# HyperLight_S_rev1_0.net
KiCad netlist of a schematic drawn in EAGLE
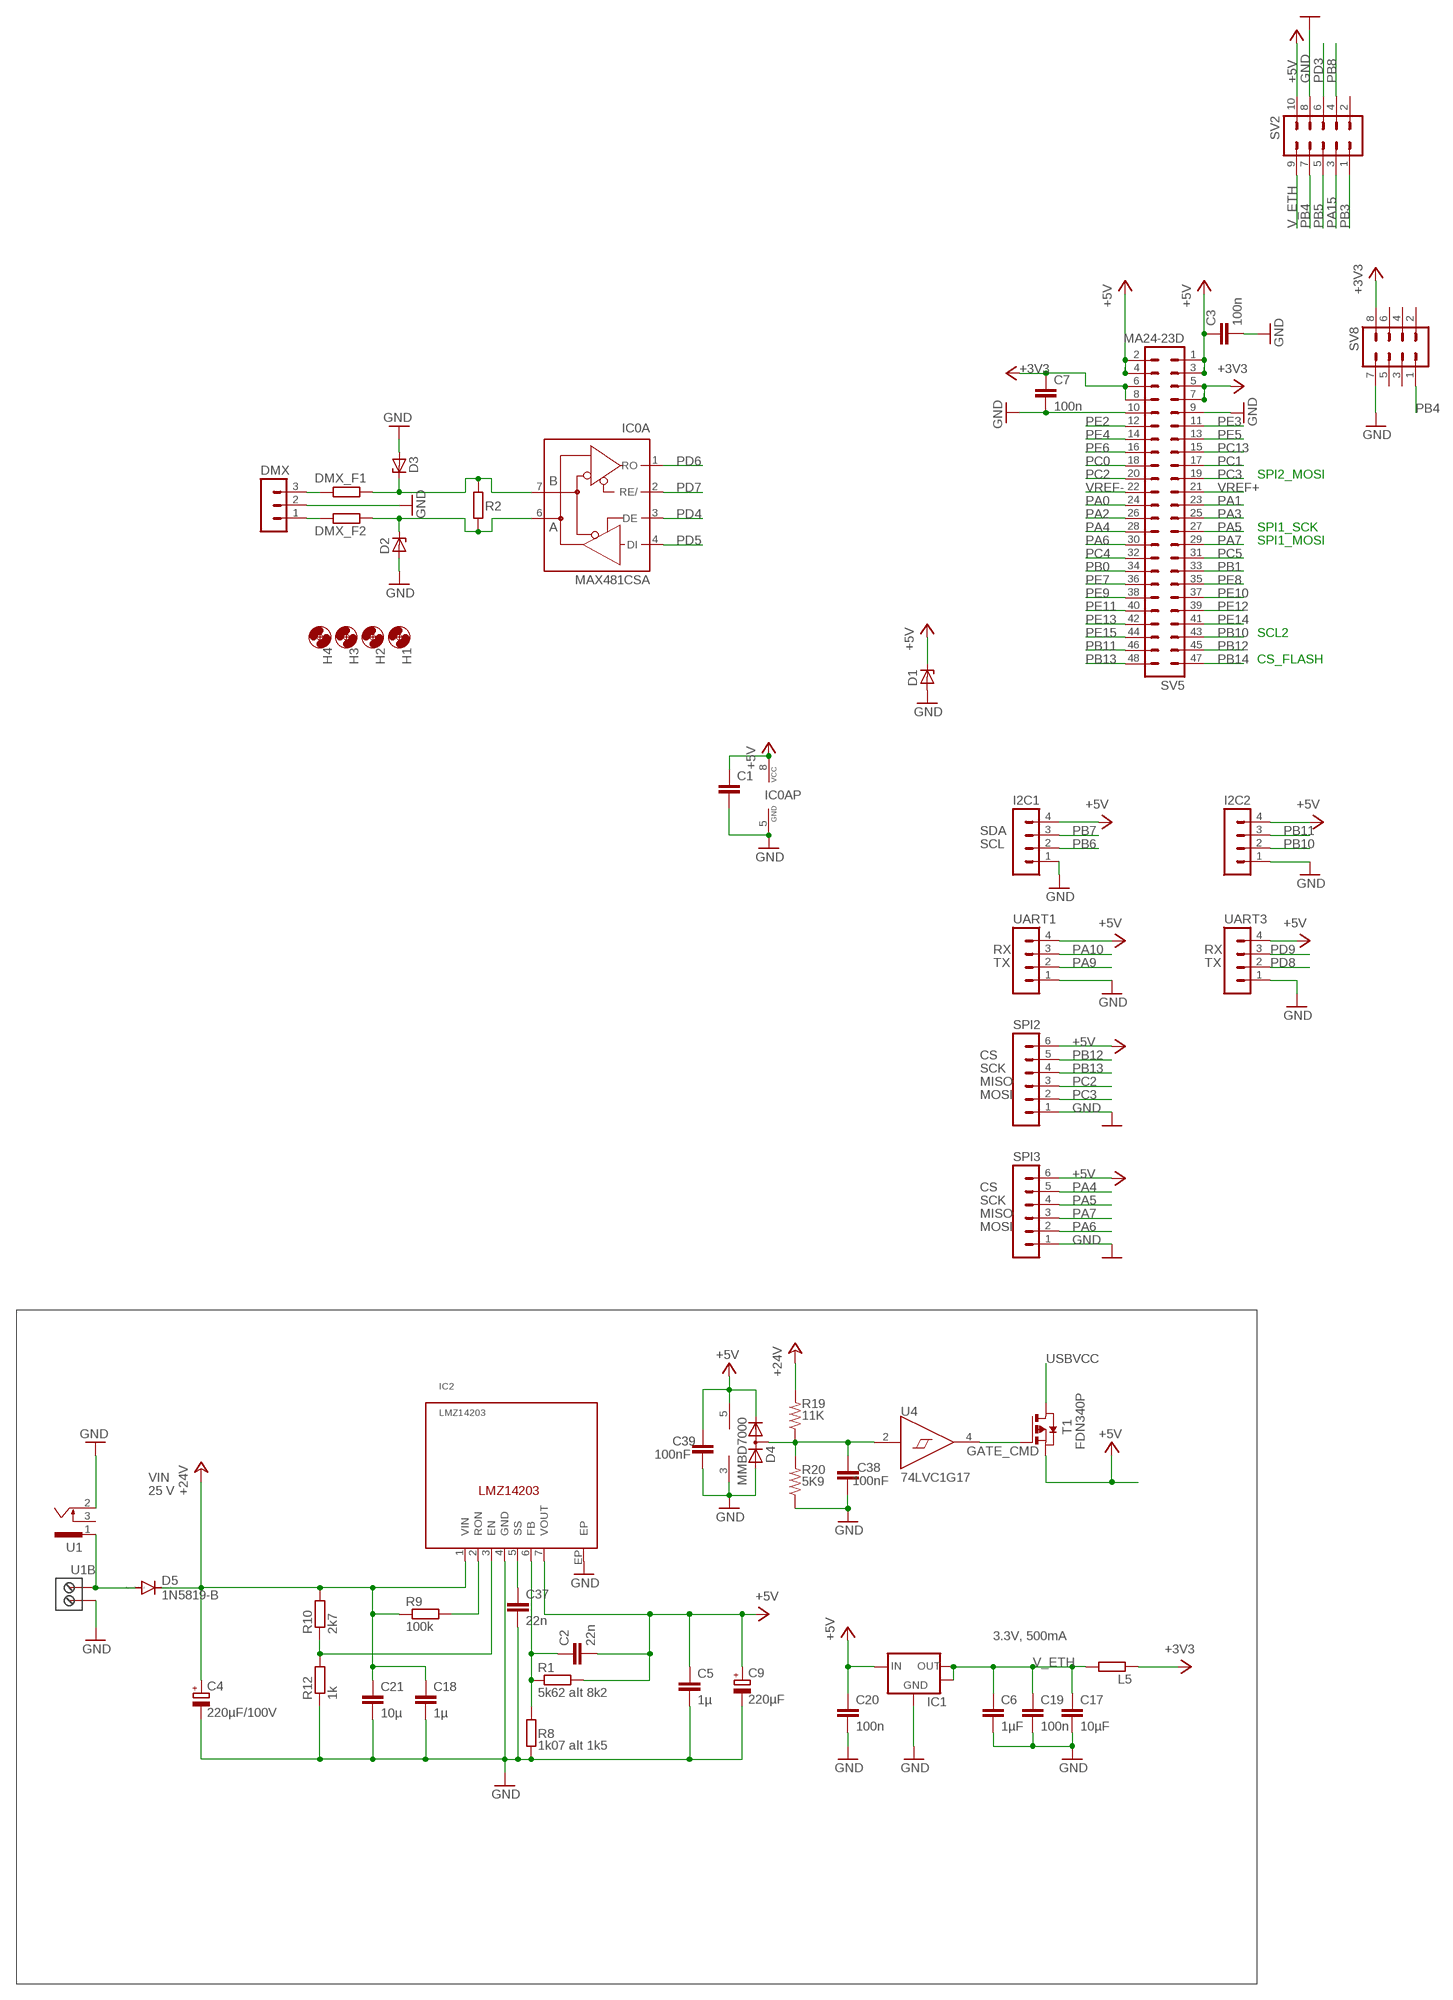
[diagram p0: schematic, sheet 1, part 1 of 2]
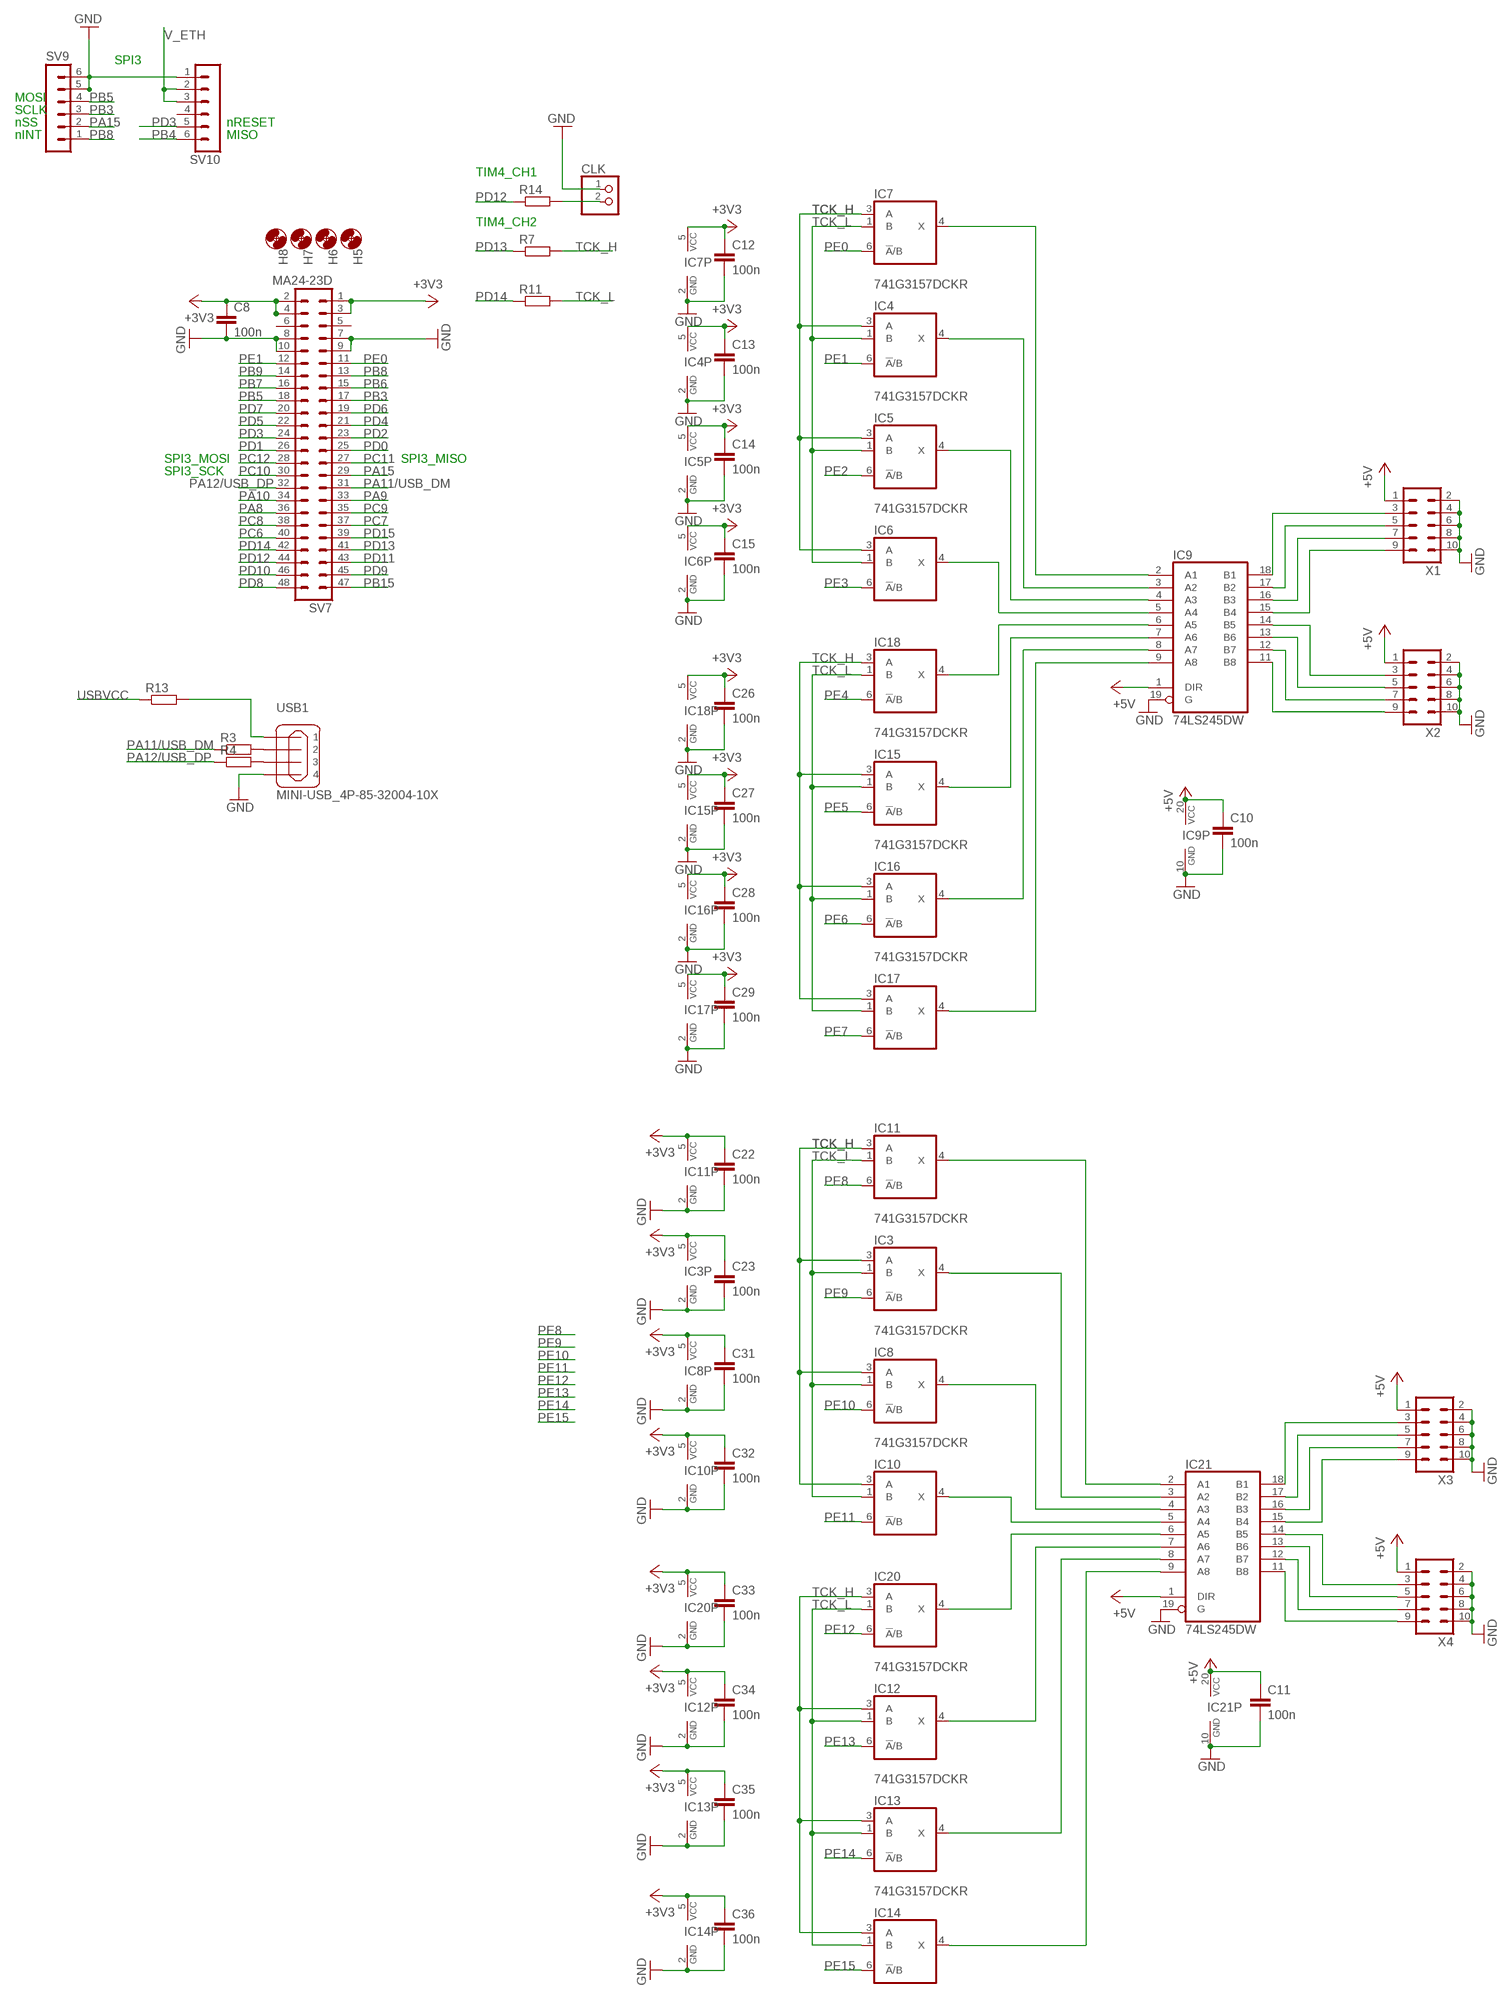
[diagram p1: schematic, sheet 1, part 2 of 2]

(export (version "E")
  (design (tool "Eeschema 10.0.6"))
  (components
    (comp (ref "C1")
      (value "C-EUC0805")
      (footprint "eagle-import:C0805")
      (libsource (lib "eagle-import") (part "rcl_C-EUC0805"))
    )
    (comp (ref "C2")
      (value "22n")
      (footprint "eagle-import:C0805")
      (libsource (lib "eagle-import") (part "rcl_334_C-EUC0805"))
    )
    (comp (ref "C3")
      (value "100n")
      (footprint "eagle-import:C0805")
      (libsource (lib "eagle-import") (part "rcl_334_C-EUC0805"))
    )
    (comp (ref "C4")
      (value "220µF/100V")
      (footprint "eagle-import:153CLV-0810")
      (libsource (lib "eagle-import") (part "CPOL-EU153CLV-0810"))
    )
    (comp (ref "C5")
      (value "1µ")
      (footprint "eagle-import:C0805")
      (libsource (lib "eagle-import") (part "rcl_334_C-EUC0805"))
    )
    (comp (ref "C6")
      (value "1µF")
      (footprint "eagle-import:C0805")
      (fields (field (name "SPICEPREFIX") "C"))
      (libsource (lib "eagle-import") (part "rcl_334_C-EUC0805"))
    )
    (comp (ref "C7")
      (value "100n")
      (footprint "eagle-import:C0805")
      (libsource (lib "eagle-import") (part "rcl_334_C-EUC0805"))
    )
    (comp (ref "C8")
      (value "100n")
      (footprint "eagle-import:C0805")
      (libsource (lib "eagle-import") (part "rcl_334_C-EUC0805"))
    )
    (comp (ref "C9")
      (value "220µF")
      (footprint "eagle-import:153CLV-0810")
      (libsource (lib "eagle-import") (part "CPOL-EU153CLV-0810"))
    )
    (comp (ref "C10")
      (value "100n")
      (footprint "eagle-import:C0603")
      (libsource (lib "eagle-import") (part "rcl_C-EUC0603"))
    )
    (comp (ref "C11")
      (value "100n")
      (footprint "eagle-import:C0603")
      (libsource (lib "eagle-import") (part "rcl_C-EUC0603"))
    )
    (comp (ref "C12")
      (value "100n")
      (footprint "eagle-import:C0603")
      (libsource (lib "eagle-import") (part "rcl_C-EUC0603"))
    )
    (comp (ref "C13")
      (value "100n")
      (footprint "eagle-import:C0603")
      (libsource (lib "eagle-import") (part "rcl_C-EUC0603"))
    )
    (comp (ref "C14")
      (value "100n")
      (footprint "eagle-import:C0603")
      (libsource (lib "eagle-import") (part "rcl_C-EUC0603"))
    )
    (comp (ref "C15")
      (value "100n")
      (footprint "eagle-import:C0603")
      (libsource (lib "eagle-import") (part "rcl_C-EUC0603"))
    )
    (comp (ref "C17")
      (value "10µF")
      (footprint "eagle-import:C0805")
      (fields (field (name "SPICEPREFIX") "C"))
      (libsource (lib "eagle-import") (part "rcl_334_C-EUC0805"))
    )
    (comp (ref "C18")
      (value "1µ")
      (footprint "eagle-import:C0805")
      (libsource (lib "eagle-import") (part "rcl_334_C-EUC0805"))
    )
    (comp (ref "C19")
      (value "100n")
      (footprint "eagle-import:C0805")
      (fields (field (name "SPICEPREFIX") "C"))
      (libsource (lib "eagle-import") (part "rcl_334_C-EUC0805"))
    )
    (comp (ref "C20")
      (value "100n")
      (footprint "eagle-import:C0805")
      (libsource (lib "eagle-import") (part "rcl_334_C-EUC0805"))
    )
    (comp (ref "C21")
      (value "10µ")
      (footprint "eagle-import:C0805")
      (libsource (lib "eagle-import") (part "rcl_334_C-EUC0805"))
    )
    (comp (ref "C22")
      (value "100n")
      (footprint "eagle-import:C0603")
      (libsource (lib "eagle-import") (part "rcl_C-EUC0603"))
    )
    (comp (ref "C23")
      (value "100n")
      (footprint "eagle-import:C0603")
      (libsource (lib "eagle-import") (part "rcl_C-EUC0603"))
    )
    (comp (ref "C26")
      (value "100n")
      (footprint "eagle-import:C0603")
      (libsource (lib "eagle-import") (part "rcl_C-EUC0603"))
    )
    (comp (ref "C27")
      (value "100n")
      (footprint "eagle-import:C0603")
      (libsource (lib "eagle-import") (part "rcl_C-EUC0603"))
    )
    (comp (ref "C28")
      (value "100n")
      (footprint "eagle-import:C0603")
      (libsource (lib "eagle-import") (part "rcl_C-EUC0603"))
    )
    (comp (ref "C29")
      (value "100n")
      (footprint "eagle-import:C0603")
      (libsource (lib "eagle-import") (part "rcl_C-EUC0603"))
    )
    (comp (ref "C31")
      (value "100n")
      (footprint "eagle-import:C0603")
      (libsource (lib "eagle-import") (part "rcl_C-EUC0603"))
    )
    (comp (ref "C32")
      (value "100n")
      (footprint "eagle-import:C0603")
      (libsource (lib "eagle-import") (part "rcl_C-EUC0603"))
    )
    (comp (ref "C33")
      (value "100n")
      (footprint "eagle-import:C0603")
      (libsource (lib "eagle-import") (part "rcl_C-EUC0603"))
    )
    (comp (ref "C34")
      (value "100n")
      (footprint "eagle-import:C0603")
      (libsource (lib "eagle-import") (part "rcl_C-EUC0603"))
    )
    (comp (ref "C35")
      (value "100n")
      (footprint "eagle-import:C0603")
      (libsource (lib "eagle-import") (part "rcl_C-EUC0603"))
    )
    (comp (ref "C36")
      (value "100n")
      (footprint "eagle-import:C0603")
      (libsource (lib "eagle-import") (part "rcl_C-EUC0603"))
    )
    (comp (ref "C37")
      (value "22n")
      (footprint "eagle-import:C0805")
      (libsource (lib "eagle-import") (part "rcl_334_C-EUC0805"))
    )
    (comp (ref "C38")
      (value "100nF")
      (footprint "eagle-import:C0402")
      (libsource (lib "eagle-import") (part "C-EUC0402"))
    )
    (comp (ref "C39")
      (value "100nF")
      (footprint "eagle-import:C0402")
      (libsource (lib "eagle-import") (part "rcl_C-EUC0402"))
    )
    (comp (ref "CLK")
      (value "PINHD-1X2")
      (footprint "eagle-import:1X02")
      (libsource (lib "eagle-import") (part "PINHD-1X2"))
    )
    (comp (ref "D1")
      (value "ZENER-DIODESMB")
      (footprint "eagle-import:SMB")
      (libsource (lib "eagle-import") (part "ZENER-DIODESMB"))
    )
    (comp (ref "D2")
      (value "ZENER-DIODESMB")
      (footprint "eagle-import:SMB")
      (libsource (lib "eagle-import") (part "ZENER-DIODESMB"))
    )
    (comp (ref "D3")
      (value "ZENER-DIODESMB")
      (footprint "eagle-import:SMB")
      (libsource (lib "eagle-import") (part "ZENER-DIODESMB"))
    )
    (comp (ref "D4")
      (value "MMBD7000")
      (footprint "eagle-import:SC70-3-R")
      (libsource (lib "eagle-import") (part "BAV199W"))
    )
    (comp (ref "D5")
      (value "1N5819-B")
      (footprint "eagle-import:SMB")
      (libsource (lib "eagle-import") (part "ES2D"))
    )
    (comp (ref "DMX")
      (value "MA03-1")
      (footprint "eagle-import:MA03-1")
      (libsource (lib "eagle-import") (part "MA03-1"))
    )
    (comp (ref "DMX_F1")
      (value "R-EU_R0805")
      (footprint "eagle-import:R0805@1")
      (libsource (lib "eagle-import") (part "R-EU_R0805"))
    )
    (comp (ref "DMX_F2")
      (value "R-EU_R0805")
      (footprint "eagle-import:R0805@1")
      (libsource (lib "eagle-import") (part "R-EU_R0805"))
    )
    (comp (ref "H1")
      (value "MOUNT-HOLE3.2")
      (footprint "eagle-import:3,2")
      (libsource (lib "eagle-import") (part "MOUNT-HOLE3.2"))
    )
    (comp (ref "H2")
      (value "MOUNT-HOLE3.2")
      (footprint "eagle-import:3,2")
      (libsource (lib "eagle-import") (part "MOUNT-HOLE3.2"))
    )
    (comp (ref "H3")
      (value "MOUNT-HOLE3.2")
      (footprint "eagle-import:3,2")
      (libsource (lib "eagle-import") (part "MOUNT-HOLE3.2"))
    )
    (comp (ref "H4")
      (value "MOUNT-HOLE3.2")
      (footprint "eagle-import:3,2")
      (libsource (lib "eagle-import") (part "MOUNT-HOLE3.2"))
    )
    (comp (ref "H5")
      (value "MOUNT-HOLE3.2")
      (footprint "eagle-import:3,2")
      (libsource (lib "eagle-import") (part "MOUNT-HOLE3.2"))
    )
    (comp (ref "H6")
      (value "MOUNT-HOLE3.2")
      (footprint "eagle-import:3,2")
      (libsource (lib "eagle-import") (part "MOUNT-HOLE3.2"))
    )
    (comp (ref "H7")
      (value "MOUNT-HOLE3.2")
      (footprint "eagle-import:3,2")
      (libsource (lib "eagle-import") (part "MOUNT-HOLE3.2"))
    )
    (comp (ref "H8")
      (value "MOUNT-HOLE3.2")
      (footprint "eagle-import:3,2")
      (libsource (lib "eagle-import") (part "MOUNT-HOLE3.2"))
    )
    (comp (ref "I2C1")
      (value "MA04-1")
      (footprint "eagle-import:MA04-1")
      (libsource (lib "eagle-import") (part "MA04-1"))
    )
    (comp (ref "I2C2")
      (value "MA04-1")
      (footprint "eagle-import:MA04-1")
      (libsource (lib "eagle-import") (part "MA04-1"))
    )
    (comp (ref "IC0A")
      (value "MAX481CSA")
      (footprint "eagle-import:SO08")
      (fields (field (name "MF") "MAXIM"))
      (libsource (lib "eagle-import") (part "MAX481CSA"))
    )
    (comp (ref "IC1")
      (value "LM1117")
      (footprint "eagle-import:SOT223")
      (libsource (lib "eagle-import") (part "LM1117"))
    )
    (comp (ref "IC2")
      (value "LMZ14203")
      (footprint "eagle-import:TO-PMOD")
      (libsource (lib "eagle-import") (part "LMZ14203"))
    )
    (comp (ref "IC3")
      (value "741G3157DCKR")
      (footprint "eagle-import:DCK_R-PDSO-G6")
      (libsource (lib "eagle-import") (part "741G3157DCKR"))
    )
    (comp (ref "IC4")
      (value "741G3157DCKR")
      (footprint "eagle-import:DCK_R-PDSO-G6")
      (libsource (lib "eagle-import") (part "741G3157DCKR"))
    )
    (comp (ref "IC5")
      (value "741G3157DCKR")
      (footprint "eagle-import:DCK_R-PDSO-G6")
      (libsource (lib "eagle-import") (part "741G3157DCKR"))
    )
    (comp (ref "IC6")
      (value "741G3157DCKR")
      (footprint "eagle-import:DCK_R-PDSO-G6")
      (libsource (lib "eagle-import") (part "741G3157DCKR"))
    )
    (comp (ref "IC7")
      (value "741G3157DCKR")
      (footprint "eagle-import:DCK_R-PDSO-G6")
      (libsource (lib "eagle-import") (part "741G3157DCKR"))
    )
    (comp (ref "IC8")
      (value "741G3157DCKR")
      (footprint "eagle-import:DCK_R-PDSO-G6")
      (libsource (lib "eagle-import") (part "741G3157DCKR"))
    )
    (comp (ref "IC9")
      (value "74LS245DW")
      (footprint "eagle-import:SO20W")
      (libsource (lib "eagle-import") (part "74245DWLS"))
    )
    (comp (ref "IC10")
      (value "741G3157DCKR")
      (footprint "eagle-import:DCK_R-PDSO-G6")
      (libsource (lib "eagle-import") (part "741G3157DCKR"))
    )
    (comp (ref "IC11")
      (value "741G3157DCKR")
      (footprint "eagle-import:DCK_R-PDSO-G6")
      (libsource (lib "eagle-import") (part "741G3157DCKR"))
    )
    (comp (ref "IC12")
      (value "741G3157DCKR")
      (footprint "eagle-import:DCK_R-PDSO-G6")
      (libsource (lib "eagle-import") (part "741G3157DCKR"))
    )
    (comp (ref "IC13")
      (value "741G3157DCKR")
      (footprint "eagle-import:DCK_R-PDSO-G6")
      (libsource (lib "eagle-import") (part "741G3157DCKR"))
    )
    (comp (ref "IC14")
      (value "741G3157DCKR")
      (footprint "eagle-import:DCK_R-PDSO-G6")
      (libsource (lib "eagle-import") (part "741G3157DCKR"))
    )
    (comp (ref "IC15")
      (value "741G3157DCKR")
      (footprint "eagle-import:DCK_R-PDSO-G6")
      (libsource (lib "eagle-import") (part "741G3157DCKR"))
    )
    (comp (ref "IC16")
      (value "741G3157DCKR")
      (footprint "eagle-import:DCK_R-PDSO-G6")
      (libsource (lib "eagle-import") (part "741G3157DCKR"))
    )
    (comp (ref "IC17")
      (value "741G3157DCKR")
      (footprint "eagle-import:DCK_R-PDSO-G6")
      (libsource (lib "eagle-import") (part "741G3157DCKR"))
    )
    (comp (ref "IC18")
      (value "741G3157DCKR")
      (footprint "eagle-import:DCK_R-PDSO-G6")
      (libsource (lib "eagle-import") (part "741G3157DCKR"))
    )
    (comp (ref "IC20")
      (value "741G3157DCKR")
      (footprint "eagle-import:DCK_R-PDSO-G6")
      (libsource (lib "eagle-import") (part "741G3157DCKR"))
    )
    (comp (ref "IC21")
      (value "74LS245DW")
      (footprint "eagle-import:SO20W")
      (libsource (lib "eagle-import") (part "74245DWLS"))
    )
    (comp (ref "L5")
      (value "R-EU_R0603")
      (footprint "eagle-import:R0603")
      (libsource (lib "eagle-import") (part "rcl_334_R-EU_R0603"))
    )
    (comp (ref "R1")
      (value "5k62 alt 8k2")
      (footprint "eagle-import:R0805@1")
      (libsource (lib "eagle-import") (part "R-EU_R0805"))
    )
    (comp (ref "R2")
      (value "R-EU_R0805")
      (footprint "eagle-import:R0805@1")
      (libsource (lib "eagle-import") (part "R-EU_R0805"))
    )
    (comp (ref "R3")
      (value "R-EU_R0805")
      (footprint "eagle-import:R0805@1")
      (libsource (lib "eagle-import") (part "R-EU_R0805"))
    )
    (comp (ref "R4")
      (value "R-EU_R0805")
      (footprint "eagle-import:R0805@1")
      (libsource (lib "eagle-import") (part "R-EU_R0805"))
    )
    (comp (ref "R7")
      (value "R-EU_R0805")
      (footprint "eagle-import:R0805@1")
      (libsource (lib "eagle-import") (part "R-EU_R0805"))
    )
    (comp (ref "R8")
      (value "1k07 alt 1k5")
      (footprint "eagle-import:R0805@1")
      (libsource (lib "eagle-import") (part "R-EU_R0805"))
    )
    (comp (ref "R9")
      (value "100k")
      (footprint "eagle-import:R0805@1")
      (libsource (lib "eagle-import") (part "R-EU_R0805"))
    )
    (comp (ref "R10")
      (value "2k7")
      (footprint "eagle-import:R0805@1")
      (libsource (lib "eagle-import") (part "R-EU_R0805"))
    )
    (comp (ref "R11")
      (value "R-EU_R0805")
      (footprint "eagle-import:R0805@1")
      (libsource (lib "eagle-import") (part "R-EU_R0805"))
    )
    (comp (ref "R12")
      (value "1k")
      (footprint "eagle-import:R0805@1")
      (libsource (lib "eagle-import") (part "R-EU_R0805"))
    )
    (comp (ref "R13")
      (value "R-EU_R1206")
      (footprint "eagle-import:R1206@1")
      (libsource (lib "eagle-import") (part "R-EU_R1206"))
    )
    (comp (ref "R14")
      (value "R-EU_R0805")
      (footprint "eagle-import:R0805@1")
      (libsource (lib "eagle-import") (part "R-EU_R0805"))
    )
    (comp (ref "R19")
      (value "11K")
      (footprint "eagle-import:R0402")
      (libsource (lib "eagle-import") (part "R-US_R0402"))
    )
    (comp (ref "R20")
      (value "5K9")
      (footprint "eagle-import:R0402")
      (libsource (lib "eagle-import") (part "R-US_R0402"))
    )
    (comp (ref "SPI2")
      (value "MA06-1")
      (footprint "eagle-import:MA06-1")
      (libsource (lib "eagle-import") (part "MA06-1"))
    )
    (comp (ref "SPI3")
      (value "MA06-1")
      (footprint "eagle-import:MA06-1")
      (libsource (lib "eagle-import") (part "MA06-1"))
    )
    (comp (ref "SV2")
      (value "MA05-2")
      (footprint "eagle-import:MA05-2")
      (libsource (lib "eagle-import") (part "MA05-2"))
    )
    (comp (ref "SV5")
      (value "MA24-23D")
      (footprint "eagle-import:HDRVR48W64P254_2X24_6096X508X762B")
      (libsource (lib "eagle-import") (part "MA24-23D"))
    )
    (comp (ref "SV7")
      (value "MA24-23D")
      (footprint "eagle-import:HDRVR48W64P254_2X24_6096X508X762B")
      (libsource (lib "eagle-import") (part "MA24-23D"))
    )
    (comp (ref "SV8")
      (value "MA04-2MALE_3D")
      (footprint "eagle-import:HDRV8W64P254_2X4_1016X508X838B")
      (libsource (lib "eagle-import") (part "MA04-2MALE_3D"))
    )
    (comp (ref "SV9")
      (value "MA06-1FEMALE_3D")
      (footprint "eagle-import:HDRVR6W64P254_1X6_1524X254X762B")
      (libsource (lib "eagle-import") (part "MA06-1FEMALE_3D"))
    )
    (comp (ref "SV10")
      (value "MA06-1FEMALE_3D")
      (footprint "eagle-import:HDRVR6W64P254_1X6_1524X254X762B")
      (libsource (lib "eagle-import") (part "MA06-1FEMALE_3D"))
    )
    (comp (ref "T1")
      (value "FDN340P")
      (footprint "eagle-import:SOT-23")
      (libsource (lib "eagle-import") (part "PMOSSOT23"))
    )
    (comp (ref "U1")
      (value "733980-62")
      (footprint "eagle-import:733980-62")
      (libsource (lib "eagle-import") (part "73398?0-62"))
    )
    (comp (ref "U1B")
      (value "RIACON101-02")
      (footprint "eagle-import:RIACON101-02")
      (libsource (lib "eagle-import") (part "RIACON101-02"))
    )
    (comp (ref "U4")
      (value "74LVC1G17")
      (footprint "eagle-import:SOT-553")
      (libsource (lib "eagle-import") (part "74LVC1G17"))
    )
    (comp (ref "UART1")
      (value "MA04-1")
      (footprint "eagle-import:MA04-1")
      (libsource (lib "eagle-import") (part "MA04-1"))
    )
    (comp (ref "UART3")
      (value "MA04-1")
      (footprint "eagle-import:MA04-1")
      (libsource (lib "eagle-import") (part "MA04-1"))
    )
    (comp (ref "USB1")
      (value "MINI-USB_4P-85-32004-10X")
      (footprint "eagle-import:85-32004-10X")
      (libsource (lib "eagle-import") (part "MINI-USB_4P-85-32004-10X"))
    )
    (comp (ref "X1")
      (value "MA05-2MA05-2S")
      (footprint "eagle-import:MA05-2S")
      (libsource (lib "eagle-import") (part "MA05-2MA05-2S"))
    )
    (comp (ref "X2")
      (value "MA05-2MA05-2S")
      (footprint "eagle-import:MA05-2S")
      (libsource (lib "eagle-import") (part "MA05-2MA05-2S"))
    )
    (comp (ref "X3")
      (value "MA05-2MA05-2S")
      (footprint "eagle-import:MA05-2S")
      (libsource (lib "eagle-import") (part "MA05-2MA05-2S"))
    )
    (comp (ref "X4")
      (value "MA05-2MA05-2S")
      (footprint "eagle-import:MA05-2S")
      (libsource (lib "eagle-import") (part "MA05-2MA05-2S"))
    )
  )
  (nets
    (net (code "1") (name "+3V3") (class "Default")
      (node (ref "C12") (pin "1") (pinfunction "1_1") (pintype "passive"))
      (node (ref "C13") (pin "1") (pinfunction "1_1") (pintype "passive"))
      (node (ref "C14") (pin "1") (pinfunction "1_1") (pintype "passive"))
      (node (ref "C15") (pin "1") (pinfunction "1_1") (pintype "passive"))
      (node (ref "C22") (pin "1") (pinfunction "1_1") (pintype "passive"))
      (node (ref "C23") (pin "1") (pinfunction "1_1") (pintype "passive"))
      (node (ref "C26") (pin "1") (pinfunction "1_1") (pintype "passive"))
      (node (ref "C27") (pin "1") (pinfunction "1_1") (pintype "passive"))
      (node (ref "C28") (pin "1") (pinfunction "1_1") (pintype "passive"))
      (node (ref "C29") (pin "1") (pinfunction "1_1") (pintype "passive"))
      (node (ref "C31") (pin "1") (pinfunction "1_1") (pintype "passive"))
      (node (ref "C32") (pin "1") (pinfunction "1_1") (pintype "passive"))
      (node (ref "C33") (pin "1") (pinfunction "1_1") (pintype "passive"))
      (node (ref "C34") (pin "1") (pinfunction "1_1") (pintype "passive"))
      (node (ref "C35") (pin "1") (pinfunction "1_1") (pintype "passive"))
      (node (ref "C36") (pin "1") (pinfunction "1_1") (pintype "passive"))
      (node (ref "C7") (pin "1") (pinfunction "1_1") (pintype "passive"))
      (node (ref "C8") (pin "1") (pinfunction "1_1") (pintype "passive"))
      (node (ref "IC10") (pin "5") (pinfunction "VCC_5") (pintype "power_in"))
      (node (ref "IC11") (pin "5") (pinfunction "VCC_5") (pintype "power_in"))
      (node (ref "IC12") (pin "5") (pinfunction "VCC_5") (pintype "power_in"))
      (node (ref "IC13") (pin "5") (pinfunction "VCC_5") (pintype "power_in"))
      (node (ref "IC14") (pin "5") (pinfunction "VCC_5") (pintype "power_in"))
      (node (ref "IC15") (pin "5") (pinfunction "VCC_5") (pintype "power_in"))
      (node (ref "IC16") (pin "5") (pinfunction "VCC_5") (pintype "power_in"))
      (node (ref "IC17") (pin "5") (pinfunction "VCC_5") (pintype "power_in"))
      (node (ref "IC18") (pin "5") (pinfunction "VCC_5") (pintype "power_in"))
      (node (ref "IC20") (pin "5") (pinfunction "VCC_5") (pintype "power_in"))
      (node (ref "IC3") (pin "5") (pinfunction "VCC_5") (pintype "power_in"))
      (node (ref "IC4") (pin "5") (pinfunction "VCC_5") (pintype "power_in"))
      (node (ref "IC5") (pin "5") (pinfunction "VCC_5") (pintype "power_in"))
      (node (ref "IC6") (pin "5") (pinfunction "VCC_5") (pintype "power_in"))
      (node (ref "IC7") (pin "5") (pinfunction "VCC_5") (pintype "power_in"))
      (node (ref "IC8") (pin "5") (pinfunction "VCC_5") (pintype "power_in"))
      (node (ref "L5") (pin "1") (pinfunction "1_1") (pintype "passive"))
      (node (ref "SV5") (pin "5") (pinfunction "5_5") (pintype "passive"))
      (node (ref "SV5") (pin "6") (pinfunction "6_6") (pintype "passive"))
      (node (ref "SV5") (pin "7") (pinfunction "7_7") (pintype "passive"))
      (node (ref "SV5") (pin "8") (pinfunction "8_8") (pintype "passive"))
      (node (ref "SV7") (pin "1") (pinfunction "1_1") (pintype "passive"))
      (node (ref "SV7") (pin "2") (pinfunction "2_2") (pintype "passive"))
      (node (ref "SV7") (pin "3") (pinfunction "3_3") (pintype "passive"))
      (node (ref "SV7") (pin "4") (pinfunction "4_4") (pintype "passive"))
      (node (ref "SV8") (pin "8") (pinfunction "8_8") (pintype "passive"))
    )
    (net (code "2") (name "+5V") (class "Default")
      (node (ref "C1") (pin "1") (pinfunction "1_1") (pintype "passive"))
      (node (ref "C10") (pin "1") (pinfunction "1_1") (pintype "passive"))
      (node (ref "C11") (pin "1") (pinfunction "1_1") (pintype "passive"))
      (node (ref "C2") (pin "2") (pinfunction "2_2") (pintype "passive"))
      (node (ref "C20") (pin "1") (pinfunction "1_1") (pintype "passive"))
      (node (ref "C3") (pin "1") (pinfunction "1_1") (pintype "passive"))
      (node (ref "C39") (pin "2") (pinfunction "2_2") (pintype "passive"))
      (node (ref "C5") (pin "1") (pinfunction "1_1") (pintype "passive"))
      (node (ref "C9") (pin "+") (pinfunction "+_+") (pintype "passive"))
      (node (ref "D1") (pin "C") (pinfunction "C_C") (pintype "passive"))
      (node (ref "D4") (pin "2") (pinfunction "C_2") (pintype "passive"))
      (node (ref "I2C1") (pin "4") (pinfunction "4_4") (pintype "passive"))
      (node (ref "I2C2") (pin "4") (pinfunction "4_4") (pintype "passive"))
      (node (ref "IC0A") (pin "8") (pinfunction "VCC_8") (pintype "power_in"))
      (node (ref "IC1") (pin "3") (pinfunction "IN_3") (pintype "input"))
      (node (ref "IC2") (pin "7") (pinfunction "VOUT_7") (pintype "bidirectional"))
      (node (ref "IC21") (pin "1") (pinfunction "DIR_1") (pintype "input"))
      (node (ref "IC21") (pin "20") (pinfunction "VCC_20") (pintype "power_in"))
      (node (ref "IC9") (pin "1") (pinfunction "DIR_1") (pintype "input"))
      (node (ref "IC9") (pin "20") (pinfunction "VCC_20") (pintype "power_in"))
      (node (ref "R1") (pin "2") (pinfunction "2_2") (pintype "passive"))
      (node (ref "SPI2") (pin "6") (pinfunction "6_6") (pintype "passive"))
      (node (ref "SPI3") (pin "6") (pinfunction "6_6") (pintype "passive"))
      (node (ref "SV2") (pin "10") (pinfunction "10_10") (pintype "passive"))
      (node (ref "SV5") (pin "1") (pinfunction "1_1") (pintype "passive"))
      (node (ref "SV5") (pin "2") (pinfunction "2_2") (pintype "passive"))
      (node (ref "SV5") (pin "3") (pinfunction "3_3") (pintype "passive"))
      (node (ref "SV5") (pin "4") (pinfunction "4_4") (pintype "passive"))
      (node (ref "T1") (pin "2") (pinfunction "S_2") (pintype "passive"))
      (node (ref "U4") (pin "5") (pinfunction "VCC_5") (pintype "bidirectional"))
      (node (ref "UART1") (pin "4") (pinfunction "4_4") (pintype "passive"))
      (node (ref "UART3") (pin "4") (pinfunction "4_4") (pintype "passive"))
      (node (ref "X1") (pin "1") (pinfunction "1_1") (pintype "passive"))
      (node (ref "X2") (pin "1") (pinfunction "1_1") (pintype "passive"))
      (node (ref "X3") (pin "1") (pinfunction "1_1") (pintype "passive"))
      (node (ref "X4") (pin "1") (pinfunction "1_1") (pintype "passive"))
    )
    (net (code "3") (name "+24V") (class "Default")
      (node (ref "C18") (pin "1") (pinfunction "1_1") (pintype "passive"))
      (node (ref "C21") (pin "1") (pinfunction "1_1") (pintype "passive"))
      (node (ref "C4") (pin "+") (pinfunction "+_+") (pintype "passive"))
      (node (ref "D5") (pin "C") (pinfunction "C_C") (pintype "passive"))
      (node (ref "IC2") (pin "1") (pinfunction "VIN_1") (pintype "bidirectional"))
      (node (ref "R10") (pin "2") (pinfunction "2_2") (pintype "passive"))
      (node (ref "R19") (pin "2") (pinfunction "2_2") (pintype "passive"))
      (node (ref "R9") (pin "1") (pinfunction "1_1") (pintype "passive"))
    )
    (net (code "4") (name "/GATE_CMD") (class "Default")
      (node (ref "T1") (pin "3") (pinfunction "G_3") (pintype "passive"))
      (node (ref "U4") (pin "4") (pinfunction "Y_4") (pintype "bidirectional"))
    )
    (net (code "5") (name "/PA0") (class "Default")
      (node (ref "SV5") (pin "24") (pinfunction "24_24") (pintype "passive"))
    )
    (net (code "6") (name "/PA1") (class "Default")
      (node (ref "SV5") (pin "23") (pinfunction "23_23") (pintype "passive"))
    )
    (net (code "7") (name "/PA2") (class "Default")
      (node (ref "SV5") (pin "26") (pinfunction "26_26") (pintype "passive"))
    )
    (net (code "8") (name "/PA3") (class "Default")
      (node (ref "SV5") (pin "25") (pinfunction "25_25") (pintype "passive"))
    )
    (net (code "9") (name "/PA4") (class "Default")
      (node (ref "SPI3") (pin "5") (pinfunction "5_5") (pintype "passive"))
      (node (ref "SV5") (pin "28") (pinfunction "28_28") (pintype "passive"))
    )
    (net (code "10") (name "/PA5") (class "Default")
      (node (ref "SPI3") (pin "4") (pinfunction "4_4") (pintype "passive"))
      (node (ref "SV5") (pin "27") (pinfunction "27_27") (pintype "passive"))
    )
    (net (code "11") (name "/PA6") (class "Default")
      (node (ref "SPI3") (pin "2") (pinfunction "2_2") (pintype "passive"))
      (node (ref "SV5") (pin "30") (pinfunction "30_30") (pintype "passive"))
    )
    (net (code "12") (name "/PA7") (class "Default")
      (node (ref "SPI3") (pin "3") (pinfunction "3_3") (pintype "passive"))
      (node (ref "SV5") (pin "29") (pinfunction "29_29") (pintype "passive"))
    )
    (net (code "13") (name "/PA8") (class "Default")
      (node (ref "SV7") (pin "36") (pinfunction "36_36") (pintype "passive"))
    )
    (net (code "14") (name "/PA9") (class "Default")
      (node (ref "SV7") (pin "33") (pinfunction "33_33") (pintype "passive"))
      (node (ref "UART1") (pin "2") (pinfunction "2_2") (pintype "passive"))
    )
    (net (code "15") (name "/PA10") (class "Default")
      (node (ref "SV7") (pin "34") (pinfunction "34_34") (pintype "passive"))
      (node (ref "UART1") (pin "3") (pinfunction "3_3") (pintype "passive"))
    )
    (net (code "16") (name "/PA11{slash}USB_DM") (class "Default")
      (node (ref "R3") (pin "1") (pinfunction "1_1") (pintype "passive"))
      (node (ref "SV7") (pin "31") (pinfunction "31_31") (pintype "passive"))
    )
    (net (code "17") (name "/PA12{slash}USB_DP") (class "Default")
      (node (ref "R4") (pin "1") (pinfunction "1_1") (pintype "passive"))
      (node (ref "SV7") (pin "32") (pinfunction "32_32") (pintype "passive"))
    )
    (net (code "18") (name "/PA15") (class "Default")
      (node (ref "SV2") (pin "3") (pinfunction "3_3") (pintype "passive"))
      (node (ref "SV7") (pin "29") (pinfunction "29_29") (pintype "passive"))
      (node (ref "SV9") (pin "2") (pinfunction "2_2") (pintype "passive"))
    )
    (net (code "19") (name "/PB0") (class "Default")
      (node (ref "SV5") (pin "34") (pinfunction "34_34") (pintype "passive"))
    )
    (net (code "20") (name "/PB1") (class "Default")
      (node (ref "SV5") (pin "33") (pinfunction "33_33") (pintype "passive"))
    )
    (net (code "21") (name "/PB3") (class "Default")
      (node (ref "SV2") (pin "1") (pinfunction "1_1") (pintype "passive"))
      (node (ref "SV7") (pin "17") (pinfunction "17_17") (pintype "passive"))
      (node (ref "SV9") (pin "3") (pinfunction "3_3") (pintype "passive"))
    )
    (net (code "22") (name "/PB4") (class "Default")
      (node (ref "SV10") (pin "6") (pinfunction "6_6") (pintype "passive"))
      (node (ref "SV2") (pin "7") (pinfunction "7_7") (pintype "passive"))
      (node (ref "SV8") (pin "1") (pinfunction "1_1") (pintype "passive"))
    )
    (net (code "23") (name "/PB5") (class "Default")
      (node (ref "SV2") (pin "5") (pinfunction "5_5") (pintype "passive"))
      (node (ref "SV7") (pin "18") (pinfunction "18_18") (pintype "passive"))
      (node (ref "SV9") (pin "4") (pinfunction "4_4") (pintype "passive"))
    )
    (net (code "24") (name "/PB6") (class "Default")
      (node (ref "I2C1") (pin "2") (pinfunction "2_2") (pintype "passive"))
      (node (ref "SV7") (pin "15") (pinfunction "15_15") (pintype "passive"))
    )
    (net (code "25") (name "/PB7") (class "Default")
      (node (ref "I2C1") (pin "3") (pinfunction "3_3") (pintype "passive"))
      (node (ref "SV7") (pin "16") (pinfunction "16_16") (pintype "passive"))
    )
    (net (code "26") (name "/PB8") (class "Default")
      (node (ref "SV2") (pin "4") (pinfunction "4_4") (pintype "passive"))
      (node (ref "SV7") (pin "13") (pinfunction "13_13") (pintype "passive"))
      (node (ref "SV9") (pin "1") (pinfunction "1_1") (pintype "passive"))
    )
    (net (code "27") (name "/PB9") (class "Default")
      (node (ref "SV7") (pin "14") (pinfunction "14_14") (pintype "passive"))
    )
    (net (code "28") (name "/PB10") (class "Default")
      (node (ref "I2C2") (pin "2") (pinfunction "2_2") (pintype "passive"))
      (node (ref "SV5") (pin "43") (pinfunction "43_43") (pintype "passive"))
    )
    (net (code "29") (name "/PB11") (class "Default")
      (node (ref "I2C2") (pin "3") (pinfunction "3_3") (pintype "passive"))
      (node (ref "SV5") (pin "46") (pinfunction "46_46") (pintype "passive"))
    )
    (net (code "30") (name "/PB12") (class "Default")
      (node (ref "SPI2") (pin "5") (pinfunction "5_5") (pintype "passive"))
      (node (ref "SV5") (pin "45") (pinfunction "45_45") (pintype "passive"))
    )
    (net (code "31") (name "/PB13") (class "Default")
      (node (ref "SPI2") (pin "4") (pinfunction "4_4") (pintype "passive"))
      (node (ref "SV5") (pin "48") (pinfunction "48_48") (pintype "passive"))
    )
    (net (code "32") (name "/PB14") (class "Default")
      (node (ref "SV5") (pin "47") (pinfunction "47_47") (pintype "passive"))
    )
    (net (code "33") (name "/PB15") (class "Default")
      (node (ref "SV7") (pin "47") (pinfunction "47_47") (pintype "passive"))
    )
    (net (code "34") (name "/PC0") (class "Default")
      (node (ref "SV5") (pin "18") (pinfunction "18_18") (pintype "passive"))
    )
    (net (code "35") (name "/PC1") (class "Default")
      (node (ref "SV5") (pin "17") (pinfunction "17_17") (pintype "passive"))
    )
    (net (code "36") (name "/PC2") (class "Default")
      (node (ref "SPI2") (pin "3") (pinfunction "3_3") (pintype "passive"))
      (node (ref "SV5") (pin "20") (pinfunction "20_20") (pintype "passive"))
    )
    (net (code "37") (name "/PC3") (class "Default")
      (node (ref "SPI2") (pin "2") (pinfunction "2_2") (pintype "passive"))
      (node (ref "SV5") (pin "19") (pinfunction "19_19") (pintype "passive"))
    )
    (net (code "38") (name "/PC4") (class "Default")
      (node (ref "SV5") (pin "32") (pinfunction "32_32") (pintype "passive"))
    )
    (net (code "39") (name "/PC5") (class "Default")
      (node (ref "SV5") (pin "31") (pinfunction "31_31") (pintype "passive"))
    )
    (net (code "40") (name "/PC6") (class "Default")
      (node (ref "SV7") (pin "40") (pinfunction "40_40") (pintype "passive"))
    )
    (net (code "41") (name "/PC7") (class "Default")
      (node (ref "SV7") (pin "37") (pinfunction "37_37") (pintype "passive"))
    )
    (net (code "42") (name "/PC8") (class "Default")
      (node (ref "SV7") (pin "38") (pinfunction "38_38") (pintype "passive"))
    )
    (net (code "43") (name "/PC9") (class "Default")
      (node (ref "SV7") (pin "35") (pinfunction "35_35") (pintype "passive"))
    )
    (net (code "44") (name "/PC10") (class "Default")
      (node (ref "SV7") (pin "30") (pinfunction "30_30") (pintype "passive"))
    )
    (net (code "45") (name "/PC11") (class "Default")
      (node (ref "SV7") (pin "27") (pinfunction "27_27") (pintype "passive"))
    )
    (net (code "46") (name "/PC12") (class "Default")
      (node (ref "SV7") (pin "28") (pinfunction "28_28") (pintype "passive"))
    )
    (net (code "47") (name "/PC13") (class "Default")
      (node (ref "SV5") (pin "15") (pinfunction "15_15") (pintype "passive"))
    )
    (net (code "48") (name "/PD0") (class "Default")
      (node (ref "SV7") (pin "25") (pinfunction "25_25") (pintype "passive"))
    )
    (net (code "49") (name "/PD1") (class "Default")
      (node (ref "SV7") (pin "26") (pinfunction "26_26") (pintype "passive"))
    )
    (net (code "50") (name "/PD2") (class "Default")
      (node (ref "SV7") (pin "23") (pinfunction "23_23") (pintype "passive"))
    )
    (net (code "51") (name "/PD3") (class "Default")
      (node (ref "SV10") (pin "5") (pinfunction "5_5") (pintype "passive"))
      (node (ref "SV2") (pin "6") (pinfunction "6_6") (pintype "passive"))
      (node (ref "SV7") (pin "24") (pinfunction "24_24") (pintype "passive"))
    )
    (net (code "52") (name "/PD4") (class "Default")
      (node (ref "IC0A") (pin "3") (pinfunction "DE_3") (pintype "input"))
      (node (ref "SV7") (pin "21") (pinfunction "21_21") (pintype "passive"))
    )
    (net (code "53") (name "/PD5") (class "Default")
      (node (ref "IC0A") (pin "4") (pinfunction "DI_4") (pintype "input"))
      (node (ref "SV7") (pin "22") (pinfunction "22_22") (pintype "passive"))
    )
    (net (code "54") (name "/PD6") (class "Default")
      (node (ref "IC0A") (pin "1") (pinfunction "RO_1") (pintype "output"))
      (node (ref "SV7") (pin "19") (pinfunction "19_19") (pintype "passive"))
    )
    (net (code "55") (name "/PD7") (class "Default")
      (node (ref "IC0A") (pin "2") (pinfunction "RE/_2") (pintype "input"))
      (node (ref "SV7") (pin "20") (pinfunction "20_20") (pintype "passive"))
    )
    (net (code "56") (name "/PD8") (class "Default")
      (node (ref "SV7") (pin "48") (pinfunction "48_48") (pintype "passive"))
      (node (ref "UART3") (pin "2") (pinfunction "2_2") (pintype "passive"))
    )
    (net (code "57") (name "/PD9") (class "Default")
      (node (ref "SV7") (pin "45") (pinfunction "45_45") (pintype "passive"))
      (node (ref "UART3") (pin "3") (pinfunction "3_3") (pintype "passive"))
    )
    (net (code "58") (name "/PD10") (class "Default")
      (node (ref "SV7") (pin "46") (pinfunction "46_46") (pintype "passive"))
    )
    (net (code "59") (name "/PD11") (class "Default")
      (node (ref "SV7") (pin "43") (pinfunction "43_43") (pintype "passive"))
    )
    (net (code "60") (name "/PD12") (class "Default")
      (node (ref "R14") (pin "1") (pinfunction "1_1") (pintype "passive"))
      (node (ref "SV7") (pin "44") (pinfunction "44_44") (pintype "passive"))
    )
    (net (code "61") (name "/PD13") (class "Default")
      (node (ref "R7") (pin "1") (pinfunction "1_1") (pintype "passive"))
      (node (ref "SV7") (pin "41") (pinfunction "41_41") (pintype "passive"))
    )
    (net (code "62") (name "/PD14") (class "Default")
      (node (ref "R11") (pin "1") (pinfunction "1_1") (pintype "passive"))
      (node (ref "SV7") (pin "42") (pinfunction "42_42") (pintype "passive"))
    )
    (net (code "63") (name "/PD15") (class "Default")
      (node (ref "SV7") (pin "39") (pinfunction "39_39") (pintype "passive"))
    )
    (net (code "64") (name "/PE0") (class "Default")
      (node (ref "IC7") (pin "6") (pinfunction "~{A}/B_6") (pintype "input"))
      (node (ref "SV7") (pin "11") (pinfunction "11_11") (pintype "passive"))
    )
    (net (code "65") (name "/PE1") (class "Default")
      (node (ref "IC4") (pin "6") (pinfunction "~{A}/B_6") (pintype "input"))
      (node (ref "SV7") (pin "12") (pinfunction "12_12") (pintype "passive"))
    )
    (net (code "66") (name "/PE2") (class "Default")
      (node (ref "IC5") (pin "6") (pinfunction "~{A}/B_6") (pintype "input"))
      (node (ref "SV5") (pin "12") (pinfunction "12_12") (pintype "passive"))
    )
    (net (code "67") (name "/PE3") (class "Default")
      (node (ref "IC6") (pin "6") (pinfunction "~{A}/B_6") (pintype "input"))
      (node (ref "SV5") (pin "11") (pinfunction "11_11") (pintype "passive"))
    )
    (net (code "68") (name "/PE4") (class "Default")
      (node (ref "IC18") (pin "6") (pinfunction "~{A}/B_6") (pintype "input"))
      (node (ref "SV5") (pin "14") (pinfunction "14_14") (pintype "passive"))
    )
    (net (code "69") (name "/PE5") (class "Default")
      (node (ref "IC15") (pin "6") (pinfunction "~{A}/B_6") (pintype "input"))
      (node (ref "SV5") (pin "13") (pinfunction "13_13") (pintype "passive"))
    )
    (net (code "70") (name "/PE6") (class "Default")
      (node (ref "IC16") (pin "6") (pinfunction "~{A}/B_6") (pintype "input"))
      (node (ref "SV5") (pin "16") (pinfunction "16_16") (pintype "passive"))
    )
    (net (code "71") (name "/PE7") (class "Default")
      (node (ref "IC17") (pin "6") (pinfunction "~{A}/B_6") (pintype "input"))
      (node (ref "SV5") (pin "36") (pinfunction "36_36") (pintype "passive"))
    )
    (net (code "72") (name "/PE8") (class "Default")
      (node (ref "IC11") (pin "6") (pinfunction "~{A}/B_6") (pintype "input"))
      (node (ref "SV5") (pin "35") (pinfunction "35_35") (pintype "passive"))
    )
    (net (code "73") (name "/PE9") (class "Default")
      (node (ref "IC3") (pin "6") (pinfunction "~{A}/B_6") (pintype "input"))
      (node (ref "SV5") (pin "38") (pinfunction "38_38") (pintype "passive"))
    )
    (net (code "74") (name "/PE10") (class "Default")
      (node (ref "IC8") (pin "6") (pinfunction "~{A}/B_6") (pintype "input"))
      (node (ref "SV5") (pin "37") (pinfunction "37_37") (pintype "passive"))
    )
    (net (code "75") (name "/PE11") (class "Default")
      (node (ref "IC10") (pin "6") (pinfunction "~{A}/B_6") (pintype "input"))
      (node (ref "SV5") (pin "40") (pinfunction "40_40") (pintype "passive"))
    )
    (net (code "76") (name "/PE12") (class "Default")
      (node (ref "IC20") (pin "6") (pinfunction "~{A}/B_6") (pintype "input"))
      (node (ref "SV5") (pin "39") (pinfunction "39_39") (pintype "passive"))
    )
    (net (code "77") (name "/PE13") (class "Default")
      (node (ref "IC12") (pin "6") (pinfunction "~{A}/B_6") (pintype "input"))
      (node (ref "SV5") (pin "42") (pinfunction "42_42") (pintype "passive"))
    )
    (net (code "78") (name "/PE14") (class "Default")
      (node (ref "IC13") (pin "6") (pinfunction "~{A}/B_6") (pintype "input"))
      (node (ref "SV5") (pin "41") (pinfunction "41_41") (pintype "passive"))
    )
    (net (code "79") (name "/PE15") (class "Default")
      (node (ref "IC14") (pin "6") (pinfunction "~{A}/B_6") (pintype "input"))
      (node (ref "SV5") (pin "44") (pinfunction "44_44") (pintype "passive"))
    )
    (net (code "80") (name "/TCK_H") (class "Default")
      (node (ref "IC10") (pin "3") (pinfunction "A_3") (pintype "bidirectional"))
      (node (ref "IC11") (pin "3") (pinfunction "A_3") (pintype "bidirectional"))
      (node (ref "IC12") (pin "3") (pinfunction "A_3") (pintype "bidirectional"))
      (node (ref "IC13") (pin "3") (pinfunction "A_3") (pintype "bidirectional"))
      (node (ref "IC14") (pin "3") (pinfunction "A_3") (pintype "bidirectional"))
      (node (ref "IC15") (pin "3") (pinfunction "A_3") (pintype "bidirectional"))
      (node (ref "IC16") (pin "3") (pinfunction "A_3") (pintype "bidirectional"))
      (node (ref "IC17") (pin "3") (pinfunction "A_3") (pintype "bidirectional"))
      (node (ref "IC18") (pin "3") (pinfunction "A_3") (pintype "bidirectional"))
      (node (ref "IC20") (pin "3") (pinfunction "A_3") (pintype "bidirectional"))
      (node (ref "IC3") (pin "3") (pinfunction "A_3") (pintype "bidirectional"))
      (node (ref "IC4") (pin "3") (pinfunction "A_3") (pintype "bidirectional"))
      (node (ref "IC5") (pin "3") (pinfunction "A_3") (pintype "bidirectional"))
      (node (ref "IC6") (pin "3") (pinfunction "A_3") (pintype "bidirectional"))
      (node (ref "IC7") (pin "3") (pinfunction "A_3") (pintype "bidirectional"))
      (node (ref "IC8") (pin "3") (pinfunction "A_3") (pintype "bidirectional"))
      (node (ref "R7") (pin "2") (pinfunction "2_2") (pintype "passive"))
    )
    (net (code "81") (name "/TCK_L") (class "Default")
      (node (ref "IC10") (pin "1") (pinfunction "B_1") (pintype "bidirectional"))
      (node (ref "IC11") (pin "1") (pinfunction "B_1") (pintype "bidirectional"))
      (node (ref "IC12") (pin "1") (pinfunction "B_1") (pintype "bidirectional"))
      (node (ref "IC13") (pin "1") (pinfunction "B_1") (pintype "bidirectional"))
      (node (ref "IC14") (pin "1") (pinfunction "B_1") (pintype "bidirectional"))
      (node (ref "IC15") (pin "1") (pinfunction "B_1") (pintype "bidirectional"))
      (node (ref "IC16") (pin "1") (pinfunction "B_1") (pintype "bidirectional"))
      (node (ref "IC17") (pin "1") (pinfunction "B_1") (pintype "bidirectional"))
      (node (ref "IC18") (pin "1") (pinfunction "B_1") (pintype "bidirectional"))
      (node (ref "IC20") (pin "1") (pinfunction "B_1") (pintype "bidirectional"))
      (node (ref "IC3") (pin "1") (pinfunction "B_1") (pintype "bidirectional"))
      (node (ref "IC4") (pin "1") (pinfunction "B_1") (pintype "bidirectional"))
      (node (ref "IC5") (pin "1") (pinfunction "B_1") (pintype "bidirectional"))
      (node (ref "IC6") (pin "1") (pinfunction "B_1") (pintype "bidirectional"))
      (node (ref "IC7") (pin "1") (pinfunction "B_1") (pintype "bidirectional"))
      (node (ref "IC8") (pin "1") (pinfunction "B_1") (pintype "bidirectional"))
      (node (ref "R11") (pin "2") (pinfunction "2_2") (pintype "passive"))
    )
    (net (code "82") (name "/USBVCC") (class "Default")
      (node (ref "R13") (pin "1") (pinfunction "1_1") (pintype "passive"))
      (node (ref "T1") (pin "1") (pinfunction "D_1") (pintype "passive"))
    )
    (net (code "83") (name "/VREF+") (class "Default")
      (node (ref "SV5") (pin "21") (pinfunction "21_21") (pintype "passive"))
    )
    (net (code "84") (name "/VREF-") (class "Default")
      (node (ref "SV5") (pin "22") (pinfunction "22_22") (pintype "passive"))
    )
    (net (code "85") (name "/V_ETH") (class "Default")
      (node (ref "C17") (pin "1") (pinfunction "1_1") (pintype "passive"))
      (node (ref "C19") (pin "1") (pinfunction "1_1") (pintype "passive"))
      (node (ref "C6") (pin "1") (pinfunction "1_1") (pintype "passive"))
      (node (ref "IC1") (pin "2") (pinfunction "OUT_2") (pintype "passive"))
      (node (ref "IC1") (pin "4") (pinfunction "PAD_4") (pintype "bidirectional"))
      (node (ref "L5") (pin "2") (pinfunction "2_2") (pintype "passive"))
      (node (ref "SV10") (pin "2") (pinfunction "2_2") (pintype "passive"))
      (node (ref "SV10") (pin "3") (pinfunction "3_3") (pintype "passive"))
      (node (ref "SV2") (pin "9") (pinfunction "9_9") (pintype "passive"))
    )
    (net (code "86") (name "GND") (class "Default")
      (node (ref "C1") (pin "2") (pinfunction "2_2") (pintype "passive"))
      (node (ref "C10") (pin "2") (pinfunction "2_2") (pintype "passive"))
      (node (ref "C11") (pin "2") (pinfunction "2_2") (pintype "passive"))
      (node (ref "C12") (pin "2") (pinfunction "2_2") (pintype "passive"))
      (node (ref "C13") (pin "2") (pinfunction "2_2") (pintype "passive"))
      (node (ref "C14") (pin "2") (pinfunction "2_2") (pintype "passive"))
      (node (ref "C15") (pin "2") (pinfunction "2_2") (pintype "passive"))
      (node (ref "C17") (pin "2") (pinfunction "2_2") (pintype "passive"))
      (node (ref "C18") (pin "2") (pinfunction "2_2") (pintype "passive"))
      (node (ref "C19") (pin "2") (pinfunction "2_2") (pintype "passive"))
      (node (ref "C20") (pin "2") (pinfunction "2_2") (pintype "passive"))
      (node (ref "C21") (pin "2") (pinfunction "2_2") (pintype "passive"))
      (node (ref "C22") (pin "2") (pinfunction "2_2") (pintype "passive"))
      (node (ref "C23") (pin "2") (pinfunction "2_2") (pintype "passive"))
      (node (ref "C26") (pin "2") (pinfunction "2_2") (pintype "passive"))
      (node (ref "C27") (pin "2") (pinfunction "2_2") (pintype "passive"))
      (node (ref "C28") (pin "2") (pinfunction "2_2") (pintype "passive"))
      (node (ref "C29") (pin "2") (pinfunction "2_2") (pintype "passive"))
      (node (ref "C3") (pin "2") (pinfunction "2_2") (pintype "passive"))
      (node (ref "C31") (pin "2") (pinfunction "2_2") (pintype "passive"))
      (node (ref "C32") (pin "2") (pinfunction "2_2") (pintype "passive"))
      (node (ref "C33") (pin "2") (pinfunction "2_2") (pintype "passive"))
      (node (ref "C34") (pin "2") (pinfunction "2_2") (pintype "passive"))
      (node (ref "C35") (pin "2") (pinfunction "2_2") (pintype "passive"))
      (node (ref "C36") (pin "2") (pinfunction "2_2") (pintype "passive"))
      (node (ref "C37") (pin "2") (pinfunction "2_2") (pintype "passive"))
      (node (ref "C38") (pin "1") (pinfunction "1_1") (pintype "passive"))
      (node (ref "C39") (pin "1") (pinfunction "1_1") (pintype "passive"))
      (node (ref "C4") (pin "-") (pinfunction "-_-") (pintype "passive"))
      (node (ref "C5") (pin "2") (pinfunction "2_2") (pintype "passive"))
      (node (ref "C6") (pin "2") (pinfunction "2_2") (pintype "passive"))
      (node (ref "C7") (pin "2") (pinfunction "2_2") (pintype "passive"))
      (node (ref "C8") (pin "2") (pinfunction "2_2") (pintype "passive"))
      (node (ref "C9") (pin "-") (pinfunction "-_-") (pintype "passive"))
      (node (ref "CLK") (pin "1") (pinfunction "1_1") (pintype "passive"))
      (node (ref "D1") (pin "A") (pinfunction "A_A") (pintype "passive"))
      (node (ref "D2") (pin "A") (pinfunction "A_A") (pintype "passive"))
      (node (ref "D3") (pin "A") (pinfunction "A_A") (pintype "passive"))
      (node (ref "D4") (pin "1") (pinfunction "A_1") (pintype "passive"))
      (node (ref "DMX") (pin "2") (pinfunction "2_2") (pintype "passive"))
      (node (ref "I2C1") (pin "1") (pinfunction "1_1") (pintype "passive"))
      (node (ref "I2C2") (pin "1") (pinfunction "1_1") (pintype "passive"))
      (node (ref "IC0A") (pin "5") (pinfunction "GND_5") (pintype "power_in"))
      (node (ref "IC1") (pin "1") (pinfunction "GND_1") (pintype "input"))
      (node (ref "IC10") (pin "2") (pinfunction "GND_2") (pintype "power_in"))
      (node (ref "IC11") (pin "2") (pinfunction "GND_2") (pintype "power_in"))
      (node (ref "IC12") (pin "2") (pinfunction "GND_2") (pintype "power_in"))
      (node (ref "IC13") (pin "2") (pinfunction "GND_2") (pintype "power_in"))
      (node (ref "IC14") (pin "2") (pinfunction "GND_2") (pintype "power_in"))
      (node (ref "IC15") (pin "2") (pinfunction "GND_2") (pintype "power_in"))
      (node (ref "IC16") (pin "2") (pinfunction "GND_2") (pintype "power_in"))
      (node (ref "IC17") (pin "2") (pinfunction "GND_2") (pintype "power_in"))
      (node (ref "IC18") (pin "2") (pinfunction "GND_2") (pintype "power_in"))
      (node (ref "IC2") (pin "4") (pinfunction "GND_4") (pintype "bidirectional"))
      (node (ref "IC2") (pin "EP") (pinfunction "EP_EP") (pintype "bidirectional"))
      (node (ref "IC20") (pin "2") (pinfunction "GND_2") (pintype "power_in"))
      (node (ref "IC21") (pin "10") (pinfunction "GND_10") (pintype "power_in"))
      (node (ref "IC21") (pin "19") (pinfunction "G_19") (pintype "input"))
      (node (ref "IC3") (pin "2") (pinfunction "GND_2") (pintype "power_in"))
      (node (ref "IC4") (pin "2") (pinfunction "GND_2") (pintype "power_in"))
      (node (ref "IC5") (pin "2") (pinfunction "GND_2") (pintype "power_in"))
      (node (ref "IC6") (pin "2") (pinfunction "GND_2") (pintype "power_in"))
      (node (ref "IC7") (pin "2") (pinfunction "GND_2") (pintype "power_in"))
      (node (ref "IC8") (pin "2") (pinfunction "GND_2") (pintype "power_in"))
      (node (ref "IC9") (pin "10") (pinfunction "GND_10") (pintype "power_in"))
      (node (ref "IC9") (pin "19") (pinfunction "G_19") (pintype "input"))
      (node (ref "R12") (pin "1") (pinfunction "1_1") (pintype "passive"))
      (node (ref "R20") (pin "1") (pinfunction "1_1") (pintype "passive"))
      (node (ref "R8") (pin "1") (pinfunction "1_1") (pintype "passive"))
      (node (ref "SPI2") (pin "1") (pinfunction "1_1") (pintype "passive"))
      (node (ref "SPI3") (pin "1") (pinfunction "1_1") (pintype "passive"))
      (node (ref "SV10") (pin "1") (pinfunction "1_1") (pintype "passive"))
      (node (ref "SV2") (pin "8") (pinfunction "8_8") (pintype "passive"))
      (node (ref "SV5") (pin "10") (pinfunction "10_10") (pintype "passive"))
      (node (ref "SV5") (pin "9") (pinfunction "9_9") (pintype "passive"))
      (node (ref "SV7") (pin "10") (pinfunction "10_10") (pintype "passive"))
      (node (ref "SV7") (pin "7") (pinfunction "7_7") (pintype "passive"))
      (node (ref "SV7") (pin "8") (pinfunction "8_8") (pintype "passive"))
      (node (ref "SV7") (pin "9") (pinfunction "9_9") (pintype "passive"))
      (node (ref "SV8") (pin "7") (pinfunction "7_7") (pintype "passive"))
      (node (ref "SV9") (pin "5") (pinfunction "5_5") (pintype "passive"))
      (node (ref "SV9") (pin "6") (pinfunction "6_6") (pintype "passive"))
      (node (ref "U1") (pin "2") (pinfunction "2_2") (pintype "passive"))
      (node (ref "U1B") (pin "P$2") (pinfunction "P$2_P$2") (pintype "bidirectional"))
      (node (ref "U4") (pin "3") (pinfunction "GND_3") (pintype "bidirectional"))
      (node (ref "UART1") (pin "1") (pinfunction "1_1") (pintype "passive"))
      (node (ref "UART3") (pin "1") (pinfunction "1_1") (pintype "passive"))
      (node (ref "USB1") (pin "4") (pinfunction "4_4") (pintype "passive"))
      (node (ref "X1") (pin "10") (pinfunction "10_10") (pintype "passive"))
      (node (ref "X1") (pin "2") (pinfunction "2_2") (pintype "passive"))
      (node (ref "X1") (pin "4") (pinfunction "4_4") (pintype "passive"))
      (node (ref "X1") (pin "6") (pinfunction "6_6") (pintype "passive"))
      (node (ref "X1") (pin "8") (pinfunction "8_8") (pintype "passive"))
      (node (ref "X2") (pin "10") (pinfunction "10_10") (pintype "passive"))
      (node (ref "X2") (pin "2") (pinfunction "2_2") (pintype "passive"))
      (node (ref "X2") (pin "4") (pinfunction "4_4") (pintype "passive"))
      (node (ref "X2") (pin "6") (pinfunction "6_6") (pintype "passive"))
      (node (ref "X2") (pin "8") (pinfunction "8_8") (pintype "passive"))
      (node (ref "X3") (pin "10") (pinfunction "10_10") (pintype "passive"))
      (node (ref "X3") (pin "2") (pinfunction "2_2") (pintype "passive"))
      (node (ref "X3") (pin "4") (pinfunction "4_4") (pintype "passive"))
      (node (ref "X3") (pin "6") (pinfunction "6_6") (pintype "passive"))
      (node (ref "X3") (pin "8") (pinfunction "8_8") (pintype "passive"))
      (node (ref "X4") (pin "10") (pinfunction "10_10") (pintype "passive"))
      (node (ref "X4") (pin "2") (pinfunction "2_2") (pintype "passive"))
      (node (ref "X4") (pin "4") (pinfunction "4_4") (pintype "passive"))
      (node (ref "X4") (pin "6") (pinfunction "6_6") (pintype "passive"))
      (node (ref "X4") (pin "8") (pinfunction "8_8") (pintype "passive"))
    )
    (net (code "87") (name "Net-(CLK-Pad2)") (class "Default")
      (node (ref "CLK") (pin "2") (pinfunction "2_2") (pintype "passive"))
      (node (ref "R14") (pin "2") (pinfunction "2_2") (pintype "passive"))
    )
    (net (code "88") (name "Net-(D4-AC)") (class "Default")
      (node (ref "C38") (pin "2") (pinfunction "2_2") (pintype "passive"))
      (node (ref "D4") (pin "3") (pinfunction "AC_3") (pintype "passive"))
      (node (ref "R19") (pin "1") (pinfunction "1_1") (pintype "passive"))
      (node (ref "R20") (pin "2") (pinfunction "2_2") (pintype "passive"))
      (node (ref "U4") (pin "2") (pinfunction "A_2") (pintype "bidirectional"))
    )
    (net (code "89") (name "Net-(D5-PadA)") (class "Default")
      (node (ref "D5") (pin "A") (pinfunction "A_A") (pintype "passive"))
      (node (ref "U1") (pin "1") (pinfunction "1_1") (pintype "passive"))
      (node (ref "U1B") (pin "P$1") (pinfunction "P$1_P$1") (pintype "bidirectional"))
    )
    (net (code "90") (name "Net-(DMX-Pad1)") (class "Default")
      (node (ref "DMX") (pin "1") (pinfunction "1_1") (pintype "passive"))
      (node (ref "DMX_F2") (pin "2") (pinfunction "2_2") (pintype "passive"))
    )
    (net (code "91") (name "Net-(DMX-Pad3)") (class "Default")
      (node (ref "DMX") (pin "3") (pinfunction "3_3") (pintype "passive"))
      (node (ref "DMX_F1") (pin "2") (pinfunction "2_2") (pintype "passive"))
    )
    (net (code "92") (name "Net-(IC0AA-A)") (class "Default")
      (node (ref "D2") (pin "C") (pinfunction "C_C") (pintype "passive"))
      (node (ref "DMX_F2") (pin "1") (pinfunction "1_1") (pintype "passive"))
      (node (ref "IC0A") (pin "6") (pinfunction "A_6") (pintype "passive"))
      (node (ref "R2") (pin "1") (pinfunction "1_1") (pintype "passive"))
    )
    (net (code "93") (name "Net-(IC0AA-B)") (class "Default")
      (node (ref "D3") (pin "C") (pinfunction "C_C") (pintype "passive"))
      (node (ref "DMX_F1") (pin "1") (pinfunction "1_1") (pintype "passive"))
      (node (ref "IC0A") (pin "7") (pinfunction "B_7") (pintype "passive"))
      (node (ref "R2") (pin "2") (pinfunction "2_2") (pintype "passive"))
    )
    (net (code "94") (name "Net-(IC2-EN)") (class "Default")
      (node (ref "IC2") (pin "3") (pinfunction "EN_3") (pintype "bidirectional"))
      (node (ref "R10") (pin "1") (pinfunction "1_1") (pintype "passive"))
      (node (ref "R12") (pin "2") (pinfunction "2_2") (pintype "passive"))
    )
    (net (code "95") (name "Net-(IC2-FB)") (class "Default")
      (node (ref "C2") (pin "1") (pinfunction "1_1") (pintype "passive"))
      (node (ref "IC2") (pin "6") (pinfunction "FB_6") (pintype "bidirectional"))
      (node (ref "R1") (pin "1") (pinfunction "1_1") (pintype "passive"))
      (node (ref "R8") (pin "2") (pinfunction "2_2") (pintype "passive"))
    )
    (net (code "96") (name "Net-(IC2-RON)") (class "Default")
      (node (ref "IC2") (pin "2") (pinfunction "RON_2") (pintype "bidirectional"))
      (node (ref "R9") (pin "2") (pinfunction "2_2") (pintype "passive"))
    )
    (net (code "97") (name "Net-(IC2-SS)") (class "Default")
      (node (ref "C37") (pin "1") (pinfunction "1_1") (pintype "passive"))
      (node (ref "IC2") (pin "5") (pinfunction "SS_5") (pintype "bidirectional"))
    )
    (net (code "98") (name "Net-(IC4A-X)") (class "Default")
      (node (ref "IC4") (pin "4") (pinfunction "X_4") (pintype "bidirectional"))
      (node (ref "IC9") (pin "3") (pinfunction "A2_3") (pintype "bidirectional"))
    )
    (net (code "99") (name "Net-(IC5A-X)") (class "Default")
      (node (ref "IC5") (pin "4") (pinfunction "X_4") (pintype "bidirectional"))
      (node (ref "IC9") (pin "4") (pinfunction "A3_4") (pintype "bidirectional"))
    )
    (net (code "100") (name "Net-(IC6A-X)") (class "Default")
      (node (ref "IC6") (pin "4") (pinfunction "X_4") (pintype "bidirectional"))
      (node (ref "IC9") (pin "5") (pinfunction "A4_5") (pintype "bidirectional"))
    )
    (net (code "101") (name "Net-(IC7A-X)") (class "Default")
      (node (ref "IC7") (pin "4") (pinfunction "X_4") (pintype "bidirectional"))
      (node (ref "IC9") (pin "2") (pinfunction "A1_2") (pintype "bidirectional"))
    )
    (net (code "102") (name "Net-(IC9A-B1)") (class "Default")
      (node (ref "IC9") (pin "18") (pinfunction "B1_18") (pintype "bidirectional"))
      (node (ref "X1") (pin "3") (pinfunction "3_3") (pintype "passive"))
    )
    (net (code "103") (name "Net-(IC9A-B2)") (class "Default")
      (node (ref "IC9") (pin "17") (pinfunction "B2_17") (pintype "bidirectional"))
      (node (ref "X1") (pin "5") (pinfunction "5_5") (pintype "passive"))
    )
    (net (code "104") (name "Net-(IC9A-B3)") (class "Default")
      (node (ref "IC9") (pin "16") (pinfunction "B3_16") (pintype "bidirectional"))
      (node (ref "X1") (pin "7") (pinfunction "7_7") (pintype "passive"))
    )
    (net (code "105") (name "Net-(IC9A-B4)") (class "Default")
      (node (ref "IC9") (pin "15") (pinfunction "B4_15") (pintype "bidirectional"))
      (node (ref "X1") (pin "9") (pinfunction "9_9") (pintype "passive"))
    )
    (net (code "106") (name "Net-(IC9A-B5)") (class "Default")
      (node (ref "IC9") (pin "14") (pinfunction "B5_14") (pintype "bidirectional"))
      (node (ref "X2") (pin "3") (pinfunction "3_3") (pintype "passive"))
    )
    (net (code "107") (name "Net-(IC9A-B6)") (class "Default")
      (node (ref "IC9") (pin "13") (pinfunction "B6_13") (pintype "bidirectional"))
      (node (ref "X2") (pin "5") (pinfunction "5_5") (pintype "passive"))
    )
    (net (code "108") (name "Net-(IC9A-B7)") (class "Default")
      (node (ref "IC9") (pin "12") (pinfunction "B7_12") (pintype "bidirectional"))
      (node (ref "X2") (pin "7") (pinfunction "7_7") (pintype "passive"))
    )
    (net (code "109") (name "Net-(IC9A-B8)") (class "Default")
      (node (ref "IC9") (pin "11") (pinfunction "B8_11") (pintype "bidirectional"))
      (node (ref "X2") (pin "9") (pinfunction "9_9") (pintype "passive"))
    )
    (net (code "110") (name "Net-(IC10A-X)") (class "Default")
      (node (ref "IC10") (pin "4") (pinfunction "X_4") (pintype "bidirectional"))
      (node (ref "IC21") (pin "5") (pinfunction "A4_5") (pintype "bidirectional"))
    )
    (net (code "111") (name "Net-(IC11A-X)") (class "Default")
      (node (ref "IC11") (pin "4") (pinfunction "X_4") (pintype "bidirectional"))
      (node (ref "IC21") (pin "2") (pinfunction "A1_2") (pintype "bidirectional"))
    )
    (net (code "112") (name "Net-(IC12A-X)") (class "Default")
      (node (ref "IC12") (pin "4") (pinfunction "X_4") (pintype "bidirectional"))
      (node (ref "IC21") (pin "7") (pinfunction "A6_7") (pintype "bidirectional"))
    )
    (net (code "113") (name "Net-(IC13A-X)") (class "Default")
      (node (ref "IC13") (pin "4") (pinfunction "X_4") (pintype "bidirectional"))
      (node (ref "IC21") (pin "8") (pinfunction "A7_8") (pintype "bidirectional"))
    )
    (net (code "114") (name "Net-(IC14A-X)") (class "Default")
      (node (ref "IC14") (pin "4") (pinfunction "X_4") (pintype "bidirectional"))
      (node (ref "IC21") (pin "9") (pinfunction "A8_9") (pintype "bidirectional"))
    )
    (net (code "115") (name "Net-(IC15A-X)") (class "Default")
      (node (ref "IC15") (pin "4") (pinfunction "X_4") (pintype "bidirectional"))
      (node (ref "IC9") (pin "7") (pinfunction "A6_7") (pintype "bidirectional"))
    )
    (net (code "116") (name "Net-(IC16A-X)") (class "Default")
      (node (ref "IC16") (pin "4") (pinfunction "X_4") (pintype "bidirectional"))
      (node (ref "IC9") (pin "8") (pinfunction "A7_8") (pintype "bidirectional"))
    )
    (net (code "117") (name "Net-(IC17A-X)") (class "Default")
      (node (ref "IC17") (pin "4") (pinfunction "X_4") (pintype "bidirectional"))
      (node (ref "IC9") (pin "9") (pinfunction "A8_9") (pintype "bidirectional"))
    )
    (net (code "118") (name "Net-(IC18A-X)") (class "Default")
      (node (ref "IC18") (pin "4") (pinfunction "X_4") (pintype "bidirectional"))
      (node (ref "IC9") (pin "6") (pinfunction "A5_6") (pintype "bidirectional"))
    )
    (net (code "119") (name "Net-(IC20A-X)") (class "Default")
      (node (ref "IC20") (pin "4") (pinfunction "X_4") (pintype "bidirectional"))
      (node (ref "IC21") (pin "6") (pinfunction "A5_6") (pintype "bidirectional"))
    )
    (net (code "120") (name "Net-(IC21A-A2)") (class "Default")
      (node (ref "IC21") (pin "3") (pinfunction "A2_3") (pintype "bidirectional"))
      (node (ref "IC3") (pin "4") (pinfunction "X_4") (pintype "bidirectional"))
    )
    (net (code "121") (name "Net-(IC21A-A3)") (class "Default")
      (node (ref "IC21") (pin "4") (pinfunction "A3_4") (pintype "bidirectional"))
      (node (ref "IC8") (pin "4") (pinfunction "X_4") (pintype "bidirectional"))
    )
    (net (code "122") (name "Net-(IC21A-B1)") (class "Default")
      (node (ref "IC21") (pin "18") (pinfunction "B1_18") (pintype "bidirectional"))
      (node (ref "X3") (pin "3") (pinfunction "3_3") (pintype "passive"))
    )
    (net (code "123") (name "Net-(IC21A-B2)") (class "Default")
      (node (ref "IC21") (pin "17") (pinfunction "B2_17") (pintype "bidirectional"))
      (node (ref "X3") (pin "5") (pinfunction "5_5") (pintype "passive"))
    )
    (net (code "124") (name "Net-(IC21A-B3)") (class "Default")
      (node (ref "IC21") (pin "16") (pinfunction "B3_16") (pintype "bidirectional"))
      (node (ref "X3") (pin "7") (pinfunction "7_7") (pintype "passive"))
    )
    (net (code "125") (name "Net-(IC21A-B4)") (class "Default")
      (node (ref "IC21") (pin "15") (pinfunction "B4_15") (pintype "bidirectional"))
      (node (ref "X3") (pin "9") (pinfunction "9_9") (pintype "passive"))
    )
    (net (code "126") (name "Net-(IC21A-B5)") (class "Default")
      (node (ref "IC21") (pin "14") (pinfunction "B5_14") (pintype "bidirectional"))
      (node (ref "X4") (pin "3") (pinfunction "3_3") (pintype "passive"))
    )
    (net (code "127") (name "Net-(IC21A-B6)") (class "Default")
      (node (ref "IC21") (pin "13") (pinfunction "B6_13") (pintype "bidirectional"))
      (node (ref "X4") (pin "5") (pinfunction "5_5") (pintype "passive"))
    )
    (net (code "128") (name "Net-(IC21A-B7)") (class "Default")
      (node (ref "IC21") (pin "12") (pinfunction "B7_12") (pintype "bidirectional"))
      (node (ref "X4") (pin "7") (pinfunction "7_7") (pintype "passive"))
    )
    (net (code "129") (name "Net-(IC21A-B8)") (class "Default")
      (node (ref "IC21") (pin "11") (pinfunction "B8_11") (pintype "bidirectional"))
      (node (ref "X4") (pin "9") (pinfunction "9_9") (pintype "passive"))
    )
    (net (code "130") (name "Net-(R3-Pad2)") (class "Default")
      (node (ref "R3") (pin "2") (pinfunction "2_2") (pintype "passive"))
      (node (ref "USB1") (pin "2") (pinfunction "2_2") (pintype "passive"))
    )
    (net (code "131") (name "Net-(R4-Pad2)") (class "Default")
      (node (ref "R4") (pin "2") (pinfunction "2_2") (pintype "passive"))
      (node (ref "USB1") (pin "3") (pinfunction "3_3") (pintype "passive"))
    )
    (net (code "132") (name "Net-(R13-Pad2)") (class "Default")
      (node (ref "R13") (pin "2") (pinfunction "2_2") (pintype "passive"))
      (node (ref "USB1") (pin "1") (pinfunction "1_1") (pintype "passive"))
    )
    (net (code "133") (name "unconnected-(SV2-Pad2)") (class "Default")
      (node (ref "SV2") (pin "2") (pinfunction "2_2") (pintype "passive"))
    )
    (net (code "134") (name "unconnected-(SV7-Pad5)") (class "Default")
      (node (ref "SV7") (pin "5") (pinfunction "5_5") (pintype "passive"))
    )
    (net (code "135") (name "unconnected-(SV7-Pad6)") (class "Default")
      (node (ref "SV7") (pin "6") (pinfunction "6_6") (pintype "passive"))
    )
    (net (code "136") (name "unconnected-(SV8-Pad2)") (class "Default")
      (node (ref "SV8") (pin "2") (pinfunction "2_2") (pintype "passive"))
    )
    (net (code "137") (name "unconnected-(SV8-Pad3)") (class "Default")
      (node (ref "SV8") (pin "3") (pinfunction "3_3") (pintype "passive"))
    )
    (net (code "138") (name "unconnected-(SV8-Pad4)") (class "Default")
      (node (ref "SV8") (pin "4") (pinfunction "4_4") (pintype "passive"))
    )
    (net (code "139") (name "unconnected-(SV8-Pad5)") (class "Default")
      (node (ref "SV8") (pin "5") (pinfunction "5_5") (pintype "passive"))
    )
    (net (code "140") (name "unconnected-(SV8-Pad6)") (class "Default")
      (node (ref "SV8") (pin "6") (pinfunction "6_6") (pintype "passive"))
    )
    (net (code "141") (name "unconnected-(SV10-Pad4)") (class "Default")
      (node (ref "SV10") (pin "4") (pinfunction "4_4") (pintype "passive"))
    )
    (net (code "142") (name "unconnected-(U1-Pad3)") (class "Default")
      (node (ref "U1") (pin "3") (pinfunction "3_3") (pintype "passive"))
    )
  )
)
